# Printing5.net
KiCad netlist of a schematic drawn in Altium Designer
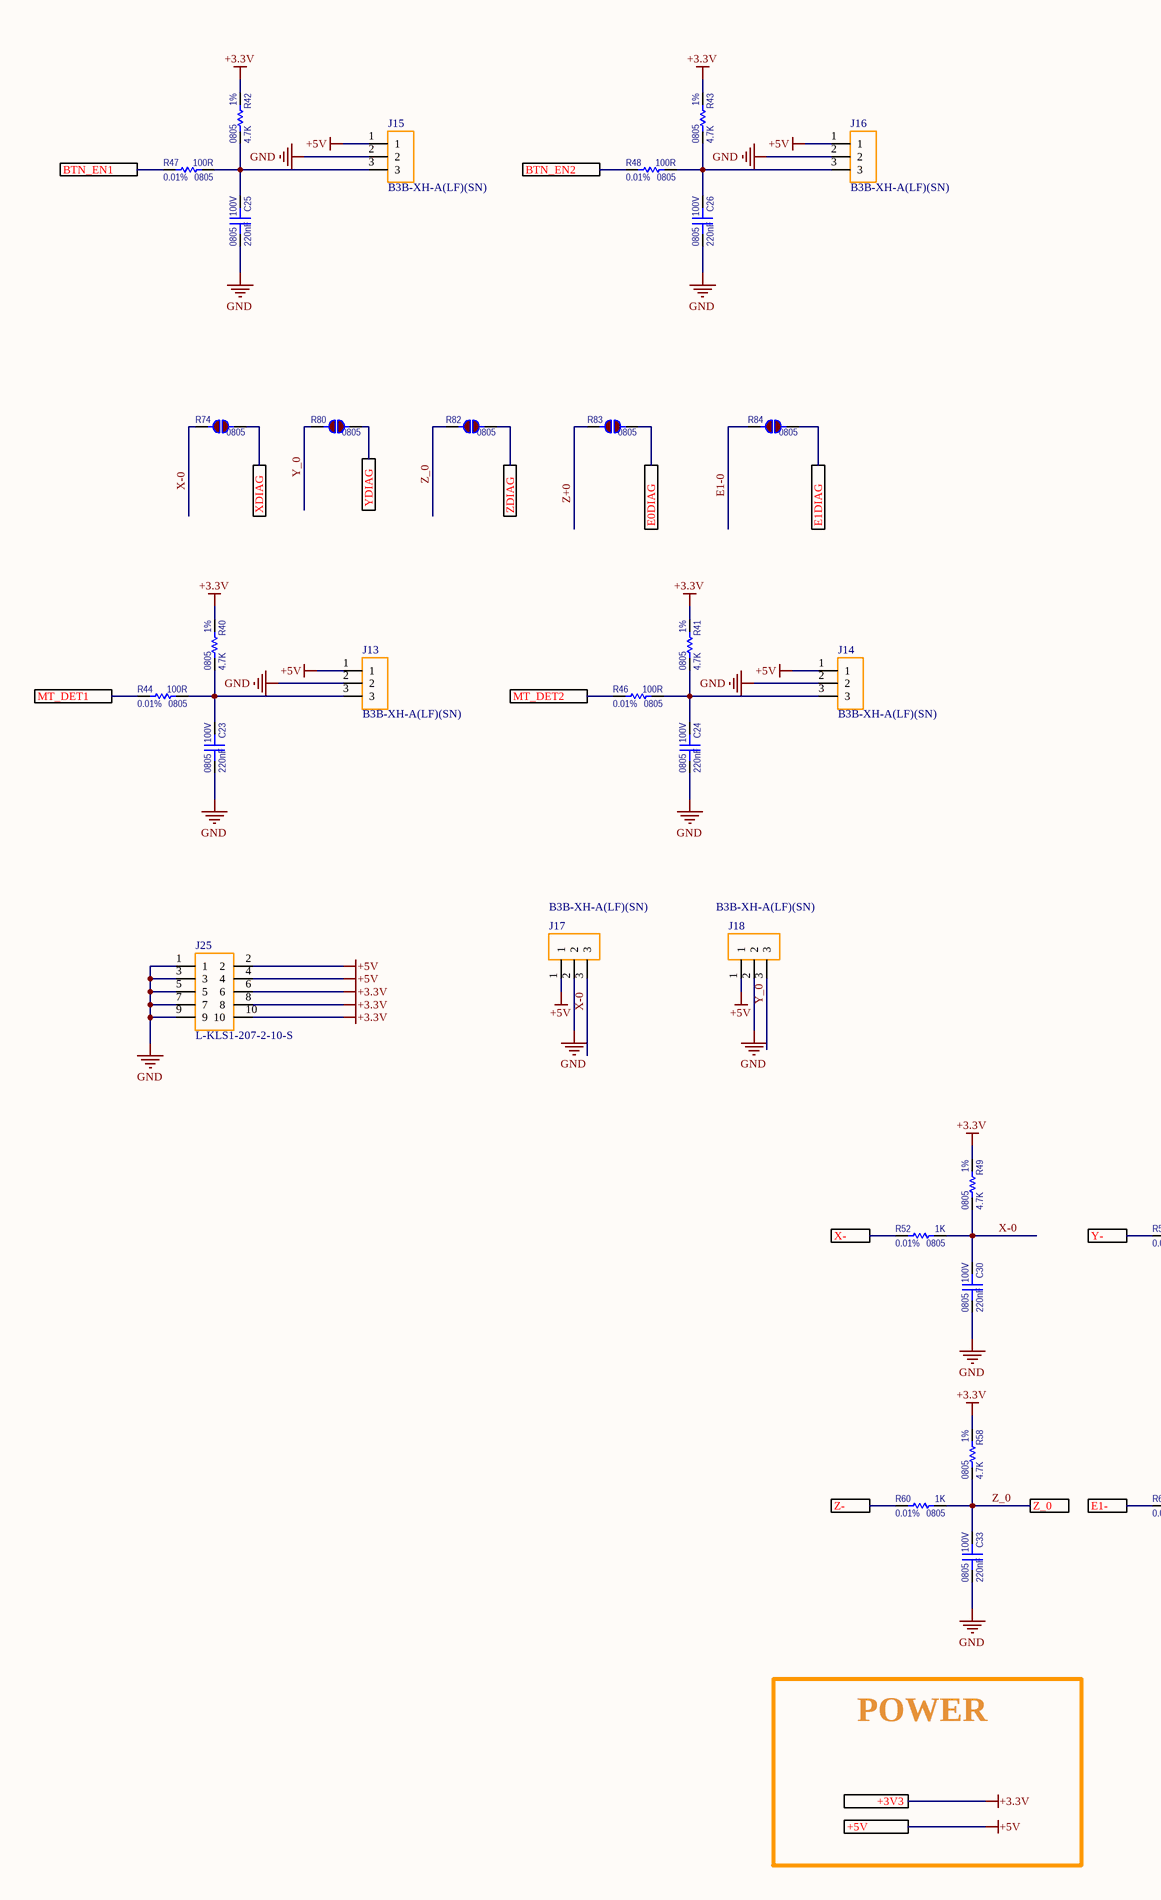
[diagram p0: Printing5.SchDoc, left]
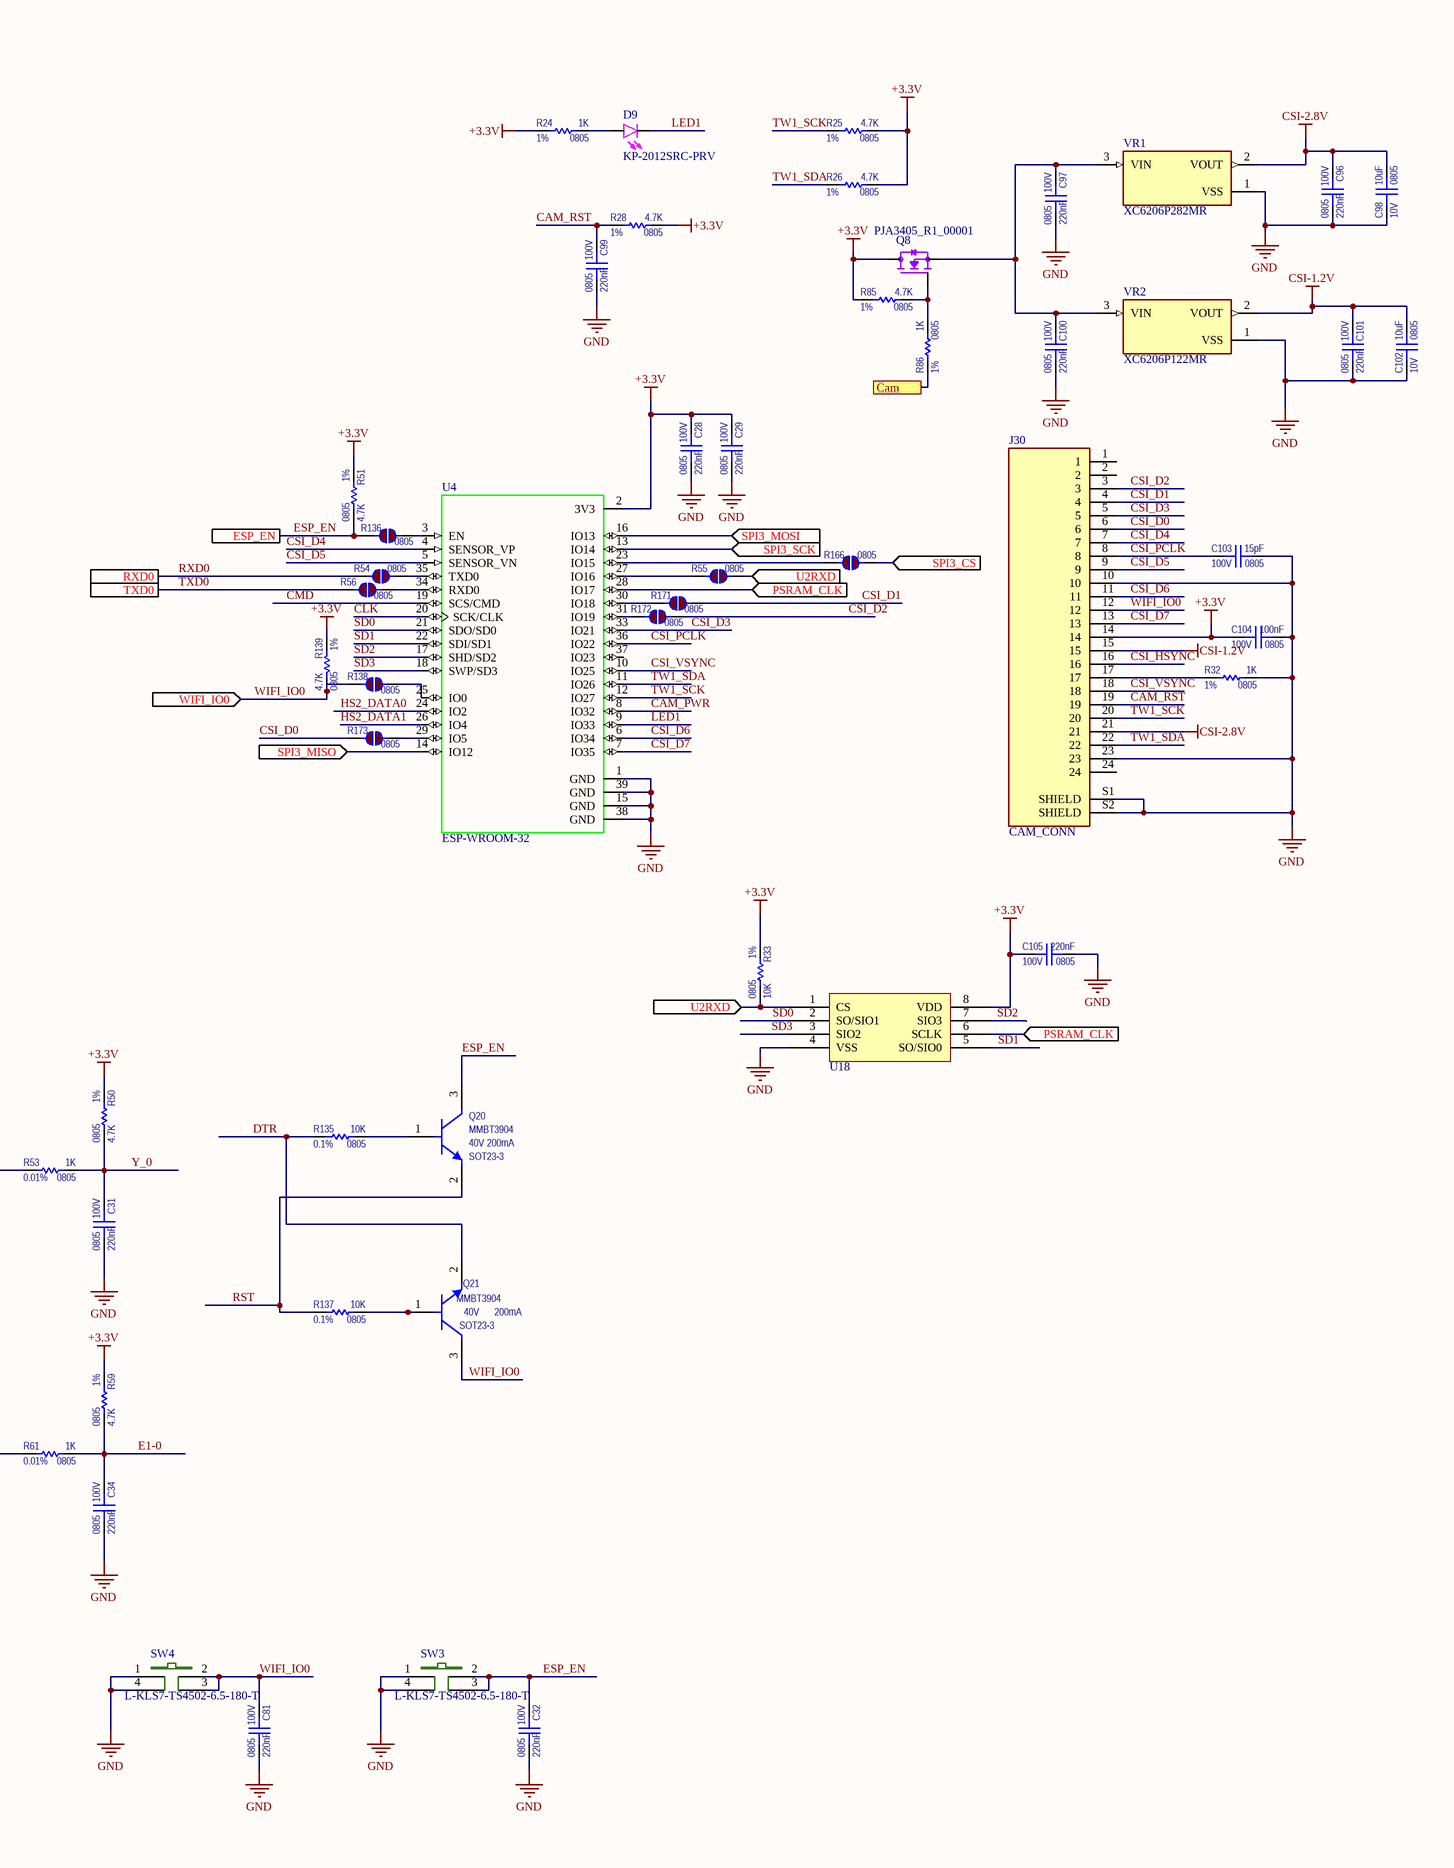
[diagram p1: Printing5.SchDoc, right]

(export (version "E")
  (design (tool "Eeschema 10.0.6"))
  (components
    (comp (ref "C23")
      (value "220nF")
      (footprint "C_0805_GEN_1.40H")
      (description "CAP_CER_220nF_100V_X7R_10%_0805")
      (fields
        (field (name "VOLTAGE") "100V")
        (field (name "PACKAGE") "0805")
        (field (name "SIMILAR PART") "CC0805KKX7R0BB224; GRM21AR72A224KAC5L")
        (field (name "TOLERANCE") "10%")
        (field (name "ADDED BY") "YasinY")
        (field (name "CHECKED BY") "İlkerU")
      )
      (libsource (lib "FireANTs_HwLibDB") (part "Capacitor"))
    )
    (comp (ref "C24")
      (value "220nF")
      (footprint "C_0805_GEN_1.40H")
      (description "CAP_CER_220nF_100V_X7R_10%_0805")
      (fields
        (field (name "VOLTAGE") "100V")
        (field (name "PACKAGE") "0805")
        (field (name "SIMILAR PART") "CC0805KKX7R0BB224; GRM21AR72A224KAC5L")
        (field (name "TOLERANCE") "10%")
        (field (name "ADDED BY") "YasinY")
        (field (name "CHECKED BY") "İlkerU")
      )
      (libsource (lib "FireANTs_HwLibDB") (part "Capacitor"))
    )
    (comp (ref "C25")
      (value "220nF")
      (footprint "C_0805_GEN_1.40H")
      (description "CAP_CER_220nF_100V_X7R_10%_0805")
      (fields
        (field (name "VOLTAGE") "100V")
        (field (name "PACKAGE") "0805")
        (field (name "SIMILAR PART") "CC0805KKX7R0BB224; GRM21AR72A224KAC5L")
        (field (name "TOLERANCE") "10%")
        (field (name "ADDED BY") "YasinY")
        (field (name "CHECKED BY") "İlkerU")
      )
      (libsource (lib "FireANTs_HwLibDB") (part "Capacitor"))
    )
    (comp (ref "C26")
      (value "220nF")
      (footprint "C_0805_GEN_1.40H")
      (description "CAP_CER_220nF_100V_X7R_10%_0805")
      (fields
        (field (name "VOLTAGE") "100V")
        (field (name "PACKAGE") "0805")
        (field (name "SIMILAR PART") "CC0805KKX7R0BB224; GRM21AR72A224KAC5L")
        (field (name "TOLERANCE") "10%")
        (field (name "ADDED BY") "YasinY")
        (field (name "CHECKED BY") "İlkerU")
      )
      (libsource (lib "FireANTs_HwLibDB") (part "Capacitor"))
    )
    (comp (ref "C28")
      (value "220nF")
      (footprint "C_0805_GEN_1.40H")
      (description "CAP_CER_220nF_100V_X7R_10%_0805")
      (fields
        (field (name "VOLTAGE") "100V")
        (field (name "PACKAGE") "0805")
        (field (name "SIMILAR PART") "CC0805KKX7R0BB224; GRM21AR72A224KAC5L")
        (field (name "TOLERANCE") "10%")
        (field (name "ADDED BY") "YasinY")
        (field (name "CHECKED BY") "İlkerU")
      )
      (libsource (lib "FireANTs_HwLibDB") (part "Capacitor"))
    )
    (comp (ref "C29")
      (value "220nF")
      (footprint "C_0805_GEN_1.40H")
      (description "CAP_CER_220nF_100V_X7R_10%_0805")
      (fields
        (field (name "VOLTAGE") "100V")
        (field (name "PACKAGE") "0805")
        (field (name "SIMILAR PART") "CC0805KKX7R0BB224; GRM21AR72A224KAC5L")
        (field (name "TOLERANCE") "10%")
        (field (name "ADDED BY") "YasinY")
        (field (name "CHECKED BY") "İlkerU")
      )
      (libsource (lib "FireANTs_HwLibDB") (part "Capacitor"))
    )
    (comp (ref "C30")
      (value "220nF")
      (footprint "C_0805_GEN_1.40H")
      (description "CAP_CER_220nF_100V_X7R_10%_0805")
      (fields
        (field (name "VOLTAGE") "100V")
        (field (name "PACKAGE") "0805")
        (field (name "SIMILAR PART") "CC0805KKX7R0BB224; GRM21AR72A224KAC5L")
        (field (name "TOLERANCE") "10%")
        (field (name "ADDED BY") "YasinY")
        (field (name "CHECKED BY") "İlkerU")
      )
      (libsource (lib "FireANTs_HwLibDB") (part "Capacitor"))
    )
    (comp (ref "C31")
      (value "220nF")
      (footprint "C_0805_GEN_1.40H")
      (description "CAP_CER_220nF_100V_X7R_10%_0805")
      (fields
        (field (name "VOLTAGE") "100V")
        (field (name "PACKAGE") "0805")
        (field (name "SIMILAR PART") "CC0805KKX7R0BB224; GRM21AR72A224KAC5L")
        (field (name "TOLERANCE") "10%")
        (field (name "ADDED BY") "YasinY")
        (field (name "CHECKED BY") "İlkerU")
      )
      (libsource (lib "FireANTs_HwLibDB") (part "Capacitor"))
    )
    (comp (ref "C32")
      (value "220nF")
      (footprint "C_0805_GEN_1.40H")
      (description "CAP_CER_220nF_100V_X7R_10%_0805")
      (fields
        (field (name "VOLTAGE") "100V")
        (field (name "PACKAGE") "0805")
        (field (name "SIMILAR PART") "CC0805KKX7R0BB224; GRM21AR72A224KAC5L")
        (field (name "TOLERANCE") "10%")
        (field (name "ADDED BY") "YasinY")
        (field (name "CHECKED BY") "İlkerU")
      )
      (libsource (lib "FireANTs_HwLibDB") (part "Capacitor"))
    )
    (comp (ref "C33")
      (value "220nF")
      (footprint "C_0805_GEN_1.40H")
      (description "CAP_CER_220nF_100V_X7R_10%_0805")
      (fields
        (field (name "VOLTAGE") "100V")
        (field (name "PACKAGE") "0805")
        (field (name "SIMILAR PART") "CC0805KKX7R0BB224; GRM21AR72A224KAC5L")
        (field (name "TOLERANCE") "10%")
        (field (name "ADDED BY") "YasinY")
        (field (name "CHECKED BY") "İlkerU")
      )
      (libsource (lib "FireANTs_HwLibDB") (part "Capacitor"))
    )
    (comp (ref "C34")
      (value "220nF")
      (footprint "C_0805_GEN_1.40H")
      (description "CAP_CER_220nF_100V_X7R_10%_0805")
      (fields
        (field (name "VOLTAGE") "100V")
        (field (name "PACKAGE") "0805")
        (field (name "SIMILAR PART") "CC0805KKX7R0BB224; GRM21AR72A224KAC5L")
        (field (name "TOLERANCE") "10%")
        (field (name "ADDED BY") "YasinY")
        (field (name "CHECKED BY") "İlkerU")
      )
      (libsource (lib "FireANTs_HwLibDB") (part "Capacitor"))
    )
    (comp (ref "C81")
      (value "220nF")
      (footprint "C_0805_GEN_1.40H")
      (description "CAP_CER_220nF_100V_X7R_10%_0805")
      (fields
        (field (name "VOLTAGE") "100V")
        (field (name "PACKAGE") "0805")
        (field (name "SIMILAR PART") "CC0805KKX7R0BB224; GRM21AR72A224KAC5L")
        (field (name "TOLERANCE") "10%")
        (field (name "ADDED BY") "YasinY")
        (field (name "CHECKED BY") "İlkerU")
      )
      (libsource (lib "FireANTs_HwLibDB") (part "Capacitor"))
    )
    (comp (ref "C96")
      (value "220nF")
      (footprint "C_0805_GEN_1.40H")
      (description "CAP_CER_220nF_100V_X7R_10%_0805")
      (fields
        (field (name "VOLTAGE") "100V")
        (field (name "PACKAGE") "0805")
        (field (name "SIMILAR PART") "CC0805KKX7R0BB224; GRM21AR72A224KAC5L")
        (field (name "TOLERANCE") "10%")
        (field (name "ADDED BY") "YasinY")
        (field (name "CHECKED BY") "İlkerU")
      )
      (libsource (lib "FireANTs_HwLibDB") (part "Capacitor"))
    )
    (comp (ref "C97")
      (value "220nF")
      (footprint "C_0805_GEN_1.40H")
      (description "CAP_CER_220nF_100V_X7R_10%_0805")
      (fields
        (field (name "VOLTAGE") "100V")
        (field (name "PACKAGE") "0805")
        (field (name "SIMILAR PART") "CC0805KKX7R0BB224; GRM21AR72A224KAC5L")
        (field (name "TOLERANCE") "10%")
        (field (name "ADDED BY") "YasinY")
        (field (name "CHECKED BY") "İlkerU")
      )
      (libsource (lib "FireANTs_HwLibDB") (part "Capacitor"))
    )
    (comp (ref "C98")
      (value "10uF")
      (footprint "C_0805_GEN_1.40H")
      (description "CAP_CER_10uF_10V_X7S_10%_0805")
      (fields
        (field (name "VOLTAGE") "10V")
        (field (name "PACKAGE") "0805")
        (field (name "SIMILAR PART") "C0805C106K8RACAUTO")
        (field (name "TOLERANCE") "10%")
        (field (name "ADDED BY") "HasanA")
        (field (name "CHECKED BY") "İlkerU")
      )
      (libsource (lib "FireANTs_HwLibDB") (part "Capacitor"))
    )
    (comp (ref "C99")
      (value "220nF")
      (footprint "C_0805_GEN_1.40H")
      (description "CAP_CER_220nF_100V_X7R_10%_0805")
      (fields
        (field (name "VOLTAGE") "100V")
        (field (name "PACKAGE") "0805")
        (field (name "SIMILAR PART") "CC0805KKX7R0BB224; GRM21AR72A224KAC5L")
        (field (name "TOLERANCE") "10%")
        (field (name "ADDED BY") "YasinY")
        (field (name "CHECKED BY") "İlkerU")
      )
      (libsource (lib "FireANTs_HwLibDB") (part "Capacitor"))
    )
    (comp (ref "C100")
      (value "220nF")
      (footprint "C_0805_GEN_1.40H")
      (description "CAP_CER_220nF_100V_X7R_10%_0805")
      (fields
        (field (name "VOLTAGE") "100V")
        (field (name "PACKAGE") "0805")
        (field (name "SIMILAR PART") "CC0805KKX7R0BB224; GRM21AR72A224KAC5L")
        (field (name "TOLERANCE") "10%")
        (field (name "ADDED BY") "YasinY")
        (field (name "CHECKED BY") "İlkerU")
      )
      (libsource (lib "FireANTs_HwLibDB") (part "Capacitor"))
    )
    (comp (ref "C101")
      (value "220nF")
      (footprint "C_0805_GEN_1.40H")
      (description "CAP_CER_220nF_100V_X7R_10%_0805")
      (fields
        (field (name "VOLTAGE") "100V")
        (field (name "PACKAGE") "0805")
        (field (name "SIMILAR PART") "CC0805KKX7R0BB224; GRM21AR72A224KAC5L")
        (field (name "TOLERANCE") "10%")
        (field (name "ADDED BY") "YasinY")
        (field (name "CHECKED BY") "İlkerU")
      )
      (libsource (lib "FireANTs_HwLibDB") (part "Capacitor"))
    )
    (comp (ref "C102")
      (value "10uF")
      (footprint "C_0805_GEN_1.40H")
      (description "CAP_CER_10uF_10V_X7S_10%_0805")
      (fields
        (field (name "VOLTAGE") "10V")
        (field (name "PACKAGE") "0805")
        (field (name "SIMILAR PART") "C0805C106K8RACAUTO")
        (field (name "TOLERANCE") "10%")
        (field (name "ADDED BY") "HasanA")
        (field (name "CHECKED BY") "İlkerU")
      )
      (libsource (lib "FireANTs_HwLibDB") (part "Capacitor"))
    )
    (comp (ref "C103")
      (value "15pF")
      (footprint "C_0805_GEN_1.40H")
      (description "CAP_CER_220nF_100V_X7R_10%_0805")
      (fields
        (field (name "VOLTAGE") "100V")
        (field (name "PACKAGE") "0805")
        (field (name "SIMILAR PART") "CC0805KKX7R0BB224; GRM21AR72A224KAC5L")
        (field (name "TOLERANCE") "10%")
        (field (name "ADDED BY") "YasinY")
        (field (name "CHECKED BY") "İlkerU")
      )
      (libsource (lib "FireANTs_HwLibDB") (part "Capacitor"))
    )
    (comp (ref "C104")
      (value "100nF")
      (footprint "C_0805_GEN_1.40H")
      (description "CAP_CER_220nF_100V_X7R_10%_0805")
      (fields
        (field (name "VOLTAGE") "100V")
        (field (name "PACKAGE") "0805")
        (field (name "SIMILAR PART") "CC0805KKX7R0BB224; GRM21AR72A224KAC5L")
        (field (name "TOLERANCE") "10%")
        (field (name "ADDED BY") "YasinY")
        (field (name "CHECKED BY") "İlkerU")
      )
      (libsource (lib "FireANTs_HwLibDB") (part "Capacitor"))
    )
    (comp (ref "C105")
      (value "220nF")
      (footprint "C_0805_GEN_1.40H")
      (description "CAP_CER_220nF_100V_X7R_10%_0805")
      (fields
        (field (name "VOLTAGE") "100V")
        (field (name "PACKAGE") "0805")
        (field (name "SIMILAR PART") "CC0805KKX7R0BB224; GRM21AR72A224KAC5L")
        (field (name "TOLERANCE") "10%")
        (field (name "ADDED BY") "YasinY")
        (field (name "CHECKED BY") "İlkerU")
      )
      (libsource (lib "FireANTs_HwLibDB") (part "Capacitor"))
    )
    (comp (ref "D9")
      (value "KP-2012SRC-PRV")
      (footprint "0805 LED")
      (description "KP-2012SRC-PRV Red LED, 640 nm 2012 (0805), Rectangle Lens SMD package")
      (fields (field (name "MANUFACTURER") "Kingbright"))
      (libsource (lib "Printing") (part "KP-2012SRC-PRV"))
    )
    (comp (ref "J13")
      (value "B3B-XH-A(LF)(SN)")
      (footprint "JST_B3B-XH-A(LF)(SN)")
      (libsource (lib "") (part "B3B-XH-A(LF)(SN)_1"))
    )
    (comp (ref "J14")
      (value "B3B-XH-A(LF)(SN)")
      (footprint "JST_B3B-XH-A(LF)(SN)")
      (libsource (lib "") (part "B3B-XH-A(LF)(SN)_1"))
    )
    (comp (ref "J15")
      (value "B3B-XH-A(LF)(SN)")
      (footprint "JST_B3B-XH-A(LF)(SN)")
      (libsource (lib "") (part "B3B-XH-A(LF)(SN)_1"))
    )
    (comp (ref "J16")
      (value "B3B-XH-A(LF)(SN)")
      (footprint "JST_B3B-XH-A(LF)(SN)")
      (libsource (lib "") (part "B3B-XH-A(LF)(SN)_1"))
    )
    (comp (ref "J17")
      (value "B3B-XH-A(LF)(SN)")
      (footprint "JST_B3B-XH-A(LF)(SN)")
      (libsource (lib "Printing") (part "B3B-XH-A(LF)(SN)"))
    )
    (comp (ref "J18")
      (value "B3B-XH-A(LF)(SN)")
      (footprint "JST_B3B-XH-A(LF)(SN)")
      (libsource (lib "Printing") (part "B3B-XH-A(LF)(SN)"))
    )
    (comp (ref "J25")
      (value "L-KLS1-207-2-10-S")
      (footprint "L-KLS1-207-2-10-S")
      (libsource (lib "Printing") (part "L-KLS1-207-2-10-S"))
    )
    (comp (ref "J30")
      (value "CAM_CONN")
      (footprint "CAM_CONN")
      (libsource (lib "Printing") (part "CAM_CONN"))
    )
    (comp (ref "Q8")
      (value "PJA3405_R1_00001")
      (footprint "PJA3405_R1_00001")
      (fields (field (name "MANUFACTURER") "Pan Jit"))
      (libsource (lib "Printing") (part "PJA3405_R1_00001"))
    )
    (comp (ref "Q20")
      (value "MMBT3904")
      (footprint "SOT23-3_MMBT3904,215")
      (description "TRA_NPN_SING_40V_200mA_VSAT300mV_SOT23-3")
      (fields
        (field (name "CURRENT") "200mA")
        (field (name "VOLTAGE") "40V")
        (field (name "PACKAGE") "SOT23-3")
        (field (name "SIMILAR PART") "SST3904HZGT116; PMBT3904,235")
        (field (name "TOLERANCE") "X")
        (field (name "ADDED BY") "HasanA")
        (field (name "CHECKED BY") "EserC")
      )
      (libsource (lib "FireANTs_HwLibDB") (part "SingleNPN_B1E2C3"))
    )
    (comp (ref "Q21")
      (value "MMBT3904")
      (footprint "SOT23-3_MMBT3904,215")
      (description "TRA_NPN_SING_40V_200mA_VSAT300mV_SOT23-3")
      (fields
        (field (name "CURRENT") "200mA")
        (field (name "VOLTAGE") "40V")
        (field (name "PACKAGE") "SOT23-3")
        (field (name "SIMILAR PART") "SST3904HZGT116; PMBT3904,235")
        (field (name "TOLERANCE") "X")
        (field (name "ADDED BY") "HasanA")
        (field (name "CHECKED BY") "EserC")
      )
      (libsource (lib "FireANTs_HwLibDB") (part "SingleNPN_B1E2C3"))
    )
    (comp (ref "R24")
      (value "1K")
      (footprint "R_0805_GEN_0.60H")
      (description "RES_STD_4.7K_0.125W_1%_100ppm_0805")
      (fields
        (field (name "TOLERANCE") "1%")
        (field (name "PACKAGE") "0805")
        (field (name "VOLTAGE") "150V")
        (field (name "Comment") "StandardResistor")
        (field (name "ADDED BY") "SonerI")
        (field (name "CHECKED BY") "YasinY")
      )
      (libsource (lib "FireANTs_HwLibDB") (part "StandardResistor"))
    )
    (comp (ref "R25")
      (value "4.7K")
      (footprint "R_0805_GEN_0.60H")
      (description "RES_STD_4.7K_0.125W_1%_100ppm_0805")
      (fields
        (field (name "TOLERANCE") "1%")
        (field (name "PACKAGE") "0805")
        (field (name "VOLTAGE") "150V")
        (field (name "Comment") "StandardResistor")
        (field (name "ADDED BY") "SonerI")
        (field (name "CHECKED BY") "YasinY")
      )
      (libsource (lib "FireANTs_HwLibDB") (part "StandardResistor"))
    )
    (comp (ref "R26")
      (value "4.7K")
      (footprint "R_0805_GEN_0.60H")
      (description "RES_STD_4.7K_0.125W_1%_100ppm_0805")
      (fields
        (field (name "TOLERANCE") "1%")
        (field (name "PACKAGE") "0805")
        (field (name "VOLTAGE") "150V")
        (field (name "Comment") "StandardResistor")
        (field (name "ADDED BY") "SonerI")
        (field (name "CHECKED BY") "YasinY")
      )
      (libsource (lib "FireANTs_HwLibDB") (part "StandardResistor"))
    )
    (comp (ref "R28")
      (value "4.7K")
      (footprint "R_0805_GEN_0.60H")
      (description "RES_STD_4.7K_0.125W_1%_100ppm_0805")
      (fields
        (field (name "TOLERANCE") "1%")
        (field (name "PACKAGE") "0805")
        (field (name "VOLTAGE") "150V")
        (field (name "Comment") "StandardResistor")
        (field (name "ADDED BY") "SonerI")
        (field (name "CHECKED BY") "YasinY")
      )
      (libsource (lib "FireANTs_HwLibDB") (part "StandardResistor"))
    )
    (comp (ref "R32")
      (value "1K")
      (footprint "R_0805_GEN_0.60H")
      (description "RES_STD_4.7K_0.125W_1%_100ppm_0805")
      (fields
        (field (name "TOLERANCE") "1%")
        (field (name "PACKAGE") "0805")
        (field (name "VOLTAGE") "150V")
        (field (name "Comment") "StandardResistor")
        (field (name "ADDED BY") "SonerI")
        (field (name "CHECKED BY") "YasinY")
      )
      (libsource (lib "FireANTs_HwLibDB") (part "StandardResistor"))
    )
    (comp (ref "R33")
      (value "10K")
      (footprint "R_0805_GEN_0.60H")
      (description "RES_STD_4.7K_0.125W_1%_100ppm_0805")
      (fields
        (field (name "TOLERANCE") "1%")
        (field (name "PACKAGE") "0805")
        (field (name "VOLTAGE") "150V")
        (field (name "Comment") "StandardResistor")
        (field (name "ADDED BY") "SonerI")
        (field (name "CHECKED BY") "YasinY")
      )
      (libsource (lib "FireANTs_HwLibDB") (part "StandardResistor"))
    )
    (comp (ref "R40")
      (value "4.7K")
      (footprint "R_0805_GEN_0.60H")
      (description "RES_STD_4.7K_0.125W_1%_100ppm_0805")
      (fields
        (field (name "TOLERANCE") "1%")
        (field (name "PACKAGE") "0805")
        (field (name "VOLTAGE") "150V")
        (field (name "Comment") "StandardResistor")
        (field (name "ADDED BY") "SonerI")
        (field (name "CHECKED BY") "YasinY")
      )
      (libsource (lib "FireANTs_HwLibDB") (part "StandardResistor"))
    )
    (comp (ref "R41")
      (value "4.7K")
      (footprint "R_0805_GEN_0.60H")
      (description "RES_STD_4.7K_0.125W_1%_100ppm_0805")
      (fields
        (field (name "TOLERANCE") "1%")
        (field (name "PACKAGE") "0805")
        (field (name "VOLTAGE") "150V")
        (field (name "Comment") "StandardResistor")
        (field (name "ADDED BY") "SonerI")
        (field (name "CHECKED BY") "YasinY")
      )
      (libsource (lib "FireANTs_HwLibDB") (part "StandardResistor"))
    )
    (comp (ref "R42")
      (value "4.7K")
      (footprint "R_0805_GEN_0.60H")
      (description "RES_STD_4.7K_0.125W_1%_100ppm_0805")
      (fields
        (field (name "TOLERANCE") "1%")
        (field (name "PACKAGE") "0805")
        (field (name "VOLTAGE") "150V")
        (field (name "Comment") "StandardResistor")
        (field (name "ADDED BY") "SonerI")
        (field (name "CHECKED BY") "YasinY")
      )
      (libsource (lib "FireANTs_HwLibDB") (part "StandardResistor"))
    )
    (comp (ref "R43")
      (value "4.7K")
      (footprint "R_0805_GEN_0.60H")
      (description "RES_STD_4.7K_0.125W_1%_100ppm_0805")
      (fields
        (field (name "TOLERANCE") "1%")
        (field (name "PACKAGE") "0805")
        (field (name "VOLTAGE") "150V")
        (field (name "Comment") "StandardResistor")
        (field (name "ADDED BY") "SonerI")
        (field (name "CHECKED BY") "YasinY")
      )
      (libsource (lib "FireANTs_HwLibDB") (part "StandardResistor"))
    )
    (comp (ref "R44")
      (value "100R")
      (footprint "R_0805_GEN_0.70H")
      (description "RES_STD_100R_0.125W_0.01%_5ppm_0805")
      (fields
        (field (name "TOLERANCE") "0.01%")
        (field (name "PACKAGE") "0805")
        (field (name "VOLTAGE") "150V")
        (field (name "Comment") "StandardResistor")
        (field (name "ADDED BY") "HasanA")
        (field (name "CHECKED BY") "YasinY")
      )
      (libsource (lib "FireANTs_HwLibDB") (part "StandardResistor"))
    )
    (comp (ref "R46")
      (value "100R")
      (footprint "R_0805_GEN_0.70H")
      (description "RES_STD_100R_0.125W_0.01%_5ppm_0805")
      (fields
        (field (name "TOLERANCE") "0.01%")
        (field (name "PACKAGE") "0805")
        (field (name "VOLTAGE") "150V")
        (field (name "Comment") "StandardResistor")
        (field (name "ADDED BY") "HasanA")
        (field (name "CHECKED BY") "YasinY")
      )
      (libsource (lib "FireANTs_HwLibDB") (part "StandardResistor"))
    )
    (comp (ref "R47")
      (value "100R")
      (footprint "R_0805_GEN_0.70H")
      (description "RES_STD_100R_0.125W_0.01%_5ppm_0805")
      (fields
        (field (name "TOLERANCE") "0.01%")
        (field (name "PACKAGE") "0805")
        (field (name "VOLTAGE") "150V")
        (field (name "Comment") "StandardResistor")
        (field (name "ADDED BY") "HasanA")
        (field (name "CHECKED BY") "YasinY")
      )
      (libsource (lib "FireANTs_HwLibDB") (part "StandardResistor"))
    )
    (comp (ref "R48")
      (value "100R")
      (footprint "R_0805_GEN_0.70H")
      (description "RES_STD_100R_0.125W_0.01%_5ppm_0805")
      (fields
        (field (name "TOLERANCE") "0.01%")
        (field (name "PACKAGE") "0805")
        (field (name "VOLTAGE") "150V")
        (field (name "Comment") "StandardResistor")
        (field (name "ADDED BY") "HasanA")
        (field (name "CHECKED BY") "YasinY")
      )
      (libsource (lib "FireANTs_HwLibDB") (part "StandardResistor"))
    )
    (comp (ref "R49")
      (value "4.7K")
      (footprint "R_0805_GEN_0.60H")
      (description "RES_STD_4.7K_0.125W_1%_100ppm_0805")
      (fields
        (field (name "TOLERANCE") "1%")
        (field (name "PACKAGE") "0805")
        (field (name "VOLTAGE") "150V")
        (field (name "Comment") "StandardResistor")
        (field (name "ADDED BY") "SonerI")
        (field (name "CHECKED BY") "YasinY")
      )
      (libsource (lib "FireANTs_HwLibDB") (part "StandardResistor"))
    )
    (comp (ref "R50")
      (value "4.7K")
      (footprint "R_0805_GEN_0.60H")
      (description "RES_STD_4.7K_0.125W_1%_100ppm_0805")
      (fields
        (field (name "TOLERANCE") "1%")
        (field (name "PACKAGE") "0805")
        (field (name "VOLTAGE") "150V")
        (field (name "Comment") "StandardResistor")
        (field (name "ADDED BY") "SonerI")
        (field (name "CHECKED BY") "YasinY")
      )
      (libsource (lib "FireANTs_HwLibDB") (part "StandardResistor"))
    )
    (comp (ref "R51")
      (value "4.7K")
      (footprint "R_0805_GEN_0.60H")
      (description "RES_STD_4.7K_0.125W_1%_100ppm_0805")
      (fields
        (field (name "TOLERANCE") "1%")
        (field (name "PACKAGE") "0805")
        (field (name "VOLTAGE") "150V")
        (field (name "Comment") "StandardResistor")
        (field (name "ADDED BY") "SonerI")
        (field (name "CHECKED BY") "YasinY")
      )
      (libsource (lib "FireANTs_HwLibDB") (part "StandardResistor"))
    )
    (comp (ref "R52")
      (value "1K")
      (footprint "R_0805_GEN_0.70H")
      (description "RES_STD_1K_0.125W_0.01%_5ppm_0805")
      (fields
        (field (name "TOLERANCE") "0.01%")
        (field (name "PACKAGE") "0805")
        (field (name "SIMILAR PART") "PLTU0805U1001LST5")
        (field (name "VOLTAGE") "150V")
        (field (name "ADDED BY") "HasanA")
        (field (name "CHECKED BY") "YasinY")
      )
      (libsource (lib "FireANTs_HwLibDB") (part "StandardResistor"))
    )
    (comp (ref "R53")
      (value "1K")
      (footprint "R_0805_GEN_0.70H")
      (description "RES_STD_1K_0.125W_0.01%_5ppm_0805")
      (fields
        (field (name "TOLERANCE") "0.01%")
        (field (name "PACKAGE") "0805")
        (field (name "SIMILAR PART") "PLTU0805U1001LST5")
        (field (name "VOLTAGE") "150V")
        (field (name "ADDED BY") "HasanA")
        (field (name "CHECKED BY") "YasinY")
      )
      (libsource (lib "FireANTs_HwLibDB") (part "StandardResistor"))
    )
    (comp (ref "R54")
      (value "StandardJumper")
      (footprint "R_0805_GEN_0.70H")
      (description "RES_STD_0R_0.125W_0805")
      (fields
        (field (name "PACKAGE") "0805")
        (field (name "TOLERANCE") "5%")
        (field (name "VOLTAGE") "150V")
        (field (name "ADDED BY") "İlhanT")
        (field (name "CHECKED BY") "YasinY")
      )
      (libsource (lib "FireANTs_HwLibDB") (part "StandardJumper"))
    )
    (comp (ref "R55")
      (value "StandardJumper")
      (footprint "R_0805_GEN_0.70H")
      (description "RES_STD_0R_0.125W_0805")
      (fields
        (field (name "PACKAGE") "0805")
        (field (name "TOLERANCE") "5%")
        (field (name "VOLTAGE") "150V")
        (field (name "ADDED BY") "İlhanT")
        (field (name "CHECKED BY") "YasinY")
      )
      (libsource (lib "FireANTs_HwLibDB") (part "StandardJumper"))
    )
    (comp (ref "R56")
      (value "StandardJumper")
      (footprint "R_0805_GEN_0.70H")
      (description "RES_STD_0R_0.125W_0805")
      (fields
        (field (name "PACKAGE") "0805")
        (field (name "TOLERANCE") "5%")
        (field (name "VOLTAGE") "150V")
        (field (name "ADDED BY") "İlhanT")
        (field (name "CHECKED BY") "YasinY")
      )
      (libsource (lib "FireANTs_HwLibDB") (part "StandardJumper"))
    )
    (comp (ref "R58")
      (value "4.7K")
      (footprint "R_0805_GEN_0.60H")
      (description "RES_STD_4.7K_0.125W_1%_100ppm_0805")
      (fields
        (field (name "TOLERANCE") "1%")
        (field (name "PACKAGE") "0805")
        (field (name "VOLTAGE") "150V")
        (field (name "Comment") "StandardResistor")
        (field (name "ADDED BY") "SonerI")
        (field (name "CHECKED BY") "YasinY")
      )
      (libsource (lib "FireANTs_HwLibDB") (part "StandardResistor"))
    )
    (comp (ref "R59")
      (value "4.7K")
      (footprint "R_0805_GEN_0.60H")
      (description "RES_STD_4.7K_0.125W_1%_100ppm_0805")
      (fields
        (field (name "TOLERANCE") "1%")
        (field (name "PACKAGE") "0805")
        (field (name "VOLTAGE") "150V")
        (field (name "Comment") "StandardResistor")
        (field (name "ADDED BY") "SonerI")
        (field (name "CHECKED BY") "YasinY")
      )
      (libsource (lib "FireANTs_HwLibDB") (part "StandardResistor"))
    )
    (comp (ref "R60")
      (value "1K")
      (footprint "R_0805_GEN_0.70H")
      (description "RES_STD_1K_0.125W_0.01%_5ppm_0805")
      (fields
        (field (name "TOLERANCE") "0.01%")
        (field (name "PACKAGE") "0805")
        (field (name "SIMILAR PART") "PLTU0805U1001LST5")
        (field (name "VOLTAGE") "150V")
        (field (name "ADDED BY") "HasanA")
        (field (name "CHECKED BY") "YasinY")
      )
      (libsource (lib "FireANTs_HwLibDB") (part "StandardResistor"))
    )
    (comp (ref "R61")
      (value "1K")
      (footprint "R_0805_GEN_0.70H")
      (description "RES_STD_1K_0.125W_0.01%_5ppm_0805")
      (fields
        (field (name "TOLERANCE") "0.01%")
        (field (name "PACKAGE") "0805")
        (field (name "SIMILAR PART") "PLTU0805U1001LST5")
        (field (name "VOLTAGE") "150V")
        (field (name "ADDED BY") "HasanA")
        (field (name "CHECKED BY") "YasinY")
      )
      (libsource (lib "FireANTs_HwLibDB") (part "StandardResistor"))
    )
    (comp (ref "R74")
      (value "StandardJumper")
      (footprint "R_0805_GEN_0.70H")
      (description "RES_STD_0R_0.125W_0805")
      (fields
        (field (name "PACKAGE") "0805")
        (field (name "TOLERANCE") "5%")
        (field (name "VOLTAGE") "150V")
        (field (name "ADDED BY") "İlhanT")
        (field (name "CHECKED BY") "YasinY")
      )
      (libsource (lib "FireANTs_HwLibDB") (part "StandardJumper"))
    )
    (comp (ref "R80")
      (value "StandardJumper")
      (footprint "R_0805_GEN_0.70H")
      (description "RES_STD_0R_0.125W_0805")
      (fields
        (field (name "PACKAGE") "0805")
        (field (name "TOLERANCE") "5%")
        (field (name "VOLTAGE") "150V")
        (field (name "ADDED BY") "İlhanT")
        (field (name "CHECKED BY") "YasinY")
      )
      (libsource (lib "FireANTs_HwLibDB") (part "StandardJumper"))
    )
    (comp (ref "R82")
      (value "StandardJumper")
      (footprint "R_0805_GEN_0.70H")
      (description "RES_STD_0R_0.125W_0805")
      (fields
        (field (name "PACKAGE") "0805")
        (field (name "TOLERANCE") "5%")
        (field (name "VOLTAGE") "150V")
        (field (name "ADDED BY") "İlhanT")
        (field (name "CHECKED BY") "YasinY")
      )
      (libsource (lib "FireANTs_HwLibDB") (part "StandardJumper"))
    )
    (comp (ref "R83")
      (value "StandardJumper")
      (footprint "R_0805_GEN_0.70H")
      (description "RES_STD_0R_0.125W_0805")
      (fields
        (field (name "PACKAGE") "0805")
        (field (name "TOLERANCE") "5%")
        (field (name "VOLTAGE") "150V")
        (field (name "ADDED BY") "İlhanT")
        (field (name "CHECKED BY") "YasinY")
      )
      (libsource (lib "FireANTs_HwLibDB") (part "StandardJumper"))
    )
    (comp (ref "R84")
      (value "StandardJumper")
      (footprint "R_0805_GEN_0.70H")
      (description "RES_STD_0R_0.125W_0805")
      (fields
        (field (name "PACKAGE") "0805")
        (field (name "TOLERANCE") "5%")
        (field (name "VOLTAGE") "150V")
        (field (name "ADDED BY") "İlhanT")
        (field (name "CHECKED BY") "YasinY")
      )
      (libsource (lib "FireANTs_HwLibDB") (part "StandardJumper"))
    )
    (comp (ref "R85")
      (value "4.7K")
      (footprint "R_0805_GEN_0.60H")
      (description "RES_STD_4.7K_0.125W_1%_100ppm_0805")
      (fields
        (field (name "TOLERANCE") "1%")
        (field (name "PACKAGE") "0805")
        (field (name "VOLTAGE") "150V")
        (field (name "Comment") "StandardResistor")
        (field (name "ADDED BY") "SonerI")
        (field (name "CHECKED BY") "YasinY")
      )
      (libsource (lib "FireANTs_HwLibDB") (part "StandardResistor"))
    )
    (comp (ref "R86")
      (value "1K")
      (footprint "R_0805_GEN_0.60H")
      (description "RES_STD_4.7K_0.125W_1%_100ppm_0805")
      (fields
        (field (name "TOLERANCE") "1%")
        (field (name "PACKAGE") "0805")
        (field (name "VOLTAGE") "150V")
        (field (name "Comment") "StandardResistor")
        (field (name "ADDED BY") "SonerI")
        (field (name "CHECKED BY") "YasinY")
      )
      (libsource (lib "FireANTs_HwLibDB") (part "StandardResistor"))
    )
    (comp (ref "R135")
      (value "10K")
      (footprint "R_0805_GEN_0.70H")
      (description "RES_STD_10K_0.125W_0.1%_25ppm_0805")
      (fields
        (field (name "TOLERANCE") "0.1%")
        (field (name "PACKAGE") "0805")
        (field (name "SIMILAR PART") "RN73C2A10KBTD")
        (field (name "VOLTAGE") "100V")
        (field (name "ADDED BY") "İlhanT")
        (field (name "CHECKED BY") "YasinY")
      )
      (libsource (lib "FireANTs_HwLibDB") (part "StandardResistor"))
    )
    (comp (ref "R136")
      (value "StandardJumper")
      (footprint "R_0805_GEN_0.70H")
      (description "RES_STD_0R_0.125W_0805")
      (fields
        (field (name "PACKAGE") "0805")
        (field (name "TOLERANCE") "5%")
        (field (name "VOLTAGE") "150V")
        (field (name "ADDED BY") "İlhanT")
        (field (name "CHECKED BY") "YasinY")
      )
      (libsource (lib "FireANTs_HwLibDB") (part "StandardJumper"))
    )
    (comp (ref "R137")
      (value "10K")
      (footprint "R_0805_GEN_0.70H")
      (description "RES_STD_10K_0.125W_0.1%_25ppm_0805")
      (fields
        (field (name "TOLERANCE") "0.1%")
        (field (name "PACKAGE") "0805")
        (field (name "SIMILAR PART") "RN73C2A10KBTD")
        (field (name "VOLTAGE") "100V")
        (field (name "ADDED BY") "İlhanT")
        (field (name "CHECKED BY") "YasinY")
      )
      (libsource (lib "FireANTs_HwLibDB") (part "StandardResistor"))
    )
    (comp (ref "R138")
      (value "StandardJumper")
      (footprint "R_0805_GEN_0.70H")
      (description "RES_STD_0R_0.125W_0805")
      (fields
        (field (name "PACKAGE") "0805")
        (field (name "TOLERANCE") "5%")
        (field (name "VOLTAGE") "150V")
        (field (name "ADDED BY") "İlhanT")
        (field (name "CHECKED BY") "YasinY")
      )
      (libsource (lib "FireANTs_HwLibDB") (part "StandardJumper"))
    )
    (comp (ref "R139")
      (value "4.7K")
      (footprint "R_0805_GEN_0.60H")
      (description "RES_STD_4.7K_0.125W_1%_100ppm_0805")
      (fields
        (field (name "TOLERANCE") "1%")
        (field (name "PACKAGE") "0805")
        (field (name "VOLTAGE") "150V")
        (field (name "Comment") "StandardResistor")
        (field (name "ADDED BY") "SonerI")
        (field (name "CHECKED BY") "YasinY")
      )
      (libsource (lib "FireANTs_HwLibDB") (part "StandardResistor"))
    )
    (comp (ref "R166")
      (value "StandardJumper")
      (footprint "R_0805_GEN_0.70H")
      (description "RES_STD_0R_0.125W_0805")
      (fields
        (field (name "PACKAGE") "0805")
        (field (name "TOLERANCE") "5%")
        (field (name "VOLTAGE") "150V")
        (field (name "ADDED BY") "İlhanT")
        (field (name "CHECKED BY") "YasinY")
      )
      (libsource (lib "FireANTs_HwLibDB") (part "StandardJumper"))
    )
    (comp (ref "R171")
      (value "StandardJumper")
      (footprint "R_0805_GEN_0.70H")
      (description "RES_STD_0R_0.125W_0805")
      (fields
        (field (name "PACKAGE") "0805")
        (field (name "TOLERANCE") "5%")
        (field (name "VOLTAGE") "150V")
        (field (name "ADDED BY") "İlhanT")
        (field (name "CHECKED BY") "YasinY")
      )
      (libsource (lib "FireANTs_HwLibDB") (part "StandardJumper"))
    )
    (comp (ref "R172")
      (value "StandardJumper")
      (footprint "R_0805_GEN_0.70H")
      (description "RES_STD_0R_0.125W_0805")
      (fields
        (field (name "PACKAGE") "0805")
        (field (name "TOLERANCE") "5%")
        (field (name "VOLTAGE") "150V")
        (field (name "ADDED BY") "İlhanT")
        (field (name "CHECKED BY") "YasinY")
      )
      (libsource (lib "FireANTs_HwLibDB") (part "StandardJumper"))
    )
    (comp (ref "R173")
      (value "StandardJumper")
      (footprint "R_0805_GEN_0.70H")
      (description "RES_STD_0R_0.125W_0805")
      (fields
        (field (name "PACKAGE") "0805")
        (field (name "TOLERANCE") "5%")
        (field (name "VOLTAGE") "150V")
        (field (name "ADDED BY") "İlhanT")
        (field (name "CHECKED BY") "YasinY")
      )
      (libsource (lib "FireANTs_HwLibDB") (part "StandardJumper"))
    )
    (comp (ref "SW3")
      (value "L-KLS7-TS4502-6.5-180-T")
      (footprint "L-KLS7-TS4502-6.5-180-T")
      (libsource (lib "Printing") (part "L-KLS7-TS4502-6.5-180-T"))
    )
    (comp (ref "SW4")
      (value "L-KLS7-TS4502-6.5-180-T")
      (footprint "L-KLS7-TS4502-6.5-180-T")
      (libsource (lib "Printing") (part "L-KLS7-TS4502-6.5-180-T"))
    )
    (comp (ref "U4")
      (value "ESP-WROOM-32")
      (footprint "ESP_DUAL")
      (libsource (lib "Printing") (part "ESP-WROOM-32"))
    )
    (comp (ref "U18")
      (value "PSRAM_ESP32")
      (footprint "SOP8")
      (libsource (lib "Printing") (part "PSRAM_ESP32"))
    )
    (comp (ref "VR1")
      (value "XC6206P282MR")
      (footprint "SOT95P280X130-3N")
      (description "Linear Voltage Regulator IC 1 Output 200mA SOT-23")
      (fields (field (name "MP") "XC6206P302MR"))
      (libsource (lib "Printing") (part "XC6206P302MR"))
    )
    (comp (ref "VR2")
      (value "XC6206P122MR")
      (footprint "SOT95P280X130-3N")
      (description "Linear Voltage Regulator IC 1 Output 200mA SOT-23")
      (fields (field (name "MP") "XC6206P302MR"))
      (libsource (lib "Printing") (part "XC6206P302MR"))
    )
  )
  (nets
    (net (code "1") (name "+3.3V") (class "Default")
      (node (ref "C104") (pin "1") (pinfunction "1_1") (pintype "passive"))
      (node (ref "C105") (pin "1") (pinfunction "1_1") (pintype "passive"))
      (node (ref "C28") (pin "1") (pinfunction "1_1") (pintype "passive"))
      (node (ref "C29") (pin "1") (pinfunction "1_1") (pintype "passive"))
      (node (ref "J25") (pin "10") (pinfunction "10_10") (pintype "passive"))
      (node (ref "J25") (pin "6") (pinfunction "6_6") (pintype "passive"))
      (node (ref "J25") (pin "8") (pinfunction "8_8") (pintype "passive"))
      (node (ref "J30") (pin "14") (pinfunction "14_14") (pintype "passive"))
      (node (ref "Q8") (pin "3") (pinfunction "D_3") (pintype "passive"))
      (node (ref "R139") (pin "1") (pinfunction "1_1") (pintype "passive"))
      (node (ref "R24") (pin "1") (pinfunction "1_1") (pintype "passive"))
      (node (ref "R25") (pin "2") (pinfunction "2_2") (pintype "passive"))
      (node (ref "R26") (pin "2") (pinfunction "2_2") (pintype "passive"))
      (node (ref "R28") (pin "2") (pinfunction "2_2") (pintype "passive"))
      (node (ref "R33") (pin "1") (pinfunction "1_1") (pintype "passive"))
      (node (ref "R40") (pin "1") (pinfunction "1_1") (pintype "passive"))
      (node (ref "R41") (pin "1") (pinfunction "1_1") (pintype "passive"))
      (node (ref "R42") (pin "1") (pinfunction "1_1") (pintype "passive"))
      (node (ref "R43") (pin "1") (pinfunction "1_1") (pintype "passive"))
      (node (ref "R49") (pin "1") (pinfunction "1_1") (pintype "passive"))
      (node (ref "R50") (pin "1") (pinfunction "1_1") (pintype "passive"))
      (node (ref "R51") (pin "1") (pinfunction "1_1") (pintype "passive"))
      (node (ref "R58") (pin "1") (pinfunction "1_1") (pintype "passive"))
      (node (ref "R59") (pin "1") (pinfunction "1_1") (pintype "passive"))
      (node (ref "R85") (pin "1") (pinfunction "1_1") (pintype "passive"))
      (node (ref "U18") (pin "8") (pinfunction "VDD_8") (pintype "passive"))
      (node (ref "U4") (pin "2") (pinfunction "3V3_2") (pintype "power_in"))
    )
    (net (code "2") (name "+5V") (class "Default")
      (node (ref "J13") (pin "1") (pinfunction "1_1") (pintype "passive"))
      (node (ref "J14") (pin "1") (pinfunction "1_1") (pintype "passive"))
      (node (ref "J15") (pin "1") (pinfunction "1_1") (pintype "passive"))
      (node (ref "J16") (pin "1") (pinfunction "1_1") (pintype "passive"))
      (node (ref "J17") (pin "1") (pinfunction "1_1") (pintype "passive"))
      (node (ref "J18") (pin "1") (pinfunction "1_1") (pintype "passive"))
      (node (ref "J25") (pin "2") (pinfunction "2_2") (pintype "passive"))
      (node (ref "J25") (pin "4") (pinfunction "4_4") (pintype "passive"))
    )
    (net (code "3") (name "/BTN_EN1") (class "Default")
      (node (ref "R47") (pin "1") (pinfunction "1_1") (pintype "passive"))
    )
    (net (code "4") (name "/BTN_EN2") (class "Default")
      (node (ref "R48") (pin "1") (pinfunction "1_1") (pintype "passive"))
    )
    (net (code "5") (name "/CAM_PWR") (class "Default")
      (node (ref "U4") (pin "8") (pinfunction "IO32_8") (pintype "bidirectional"))
    )
    (net (code "6") (name "/CAM_RST") (class "Default")
      (node (ref "C99") (pin "1") (pinfunction "1_1") (pintype "passive"))
      (node (ref "J30") (pin "19") (pinfunction "19_19") (pintype "passive"))
      (node (ref "R28") (pin "1") (pinfunction "1_1") (pintype "passive"))
    )
    (net (code "7") (name "/CLK") (class "Default")
      (node (ref "U4") (pin "20") (pinfunction "SCK/CLK_20") (pintype "bidirectional"))
    )
    (net (code "8") (name "/CMD") (class "Default")
      (node (ref "U4") (pin "19") (pinfunction "SCS/CMD_19") (pintype "bidirectional"))
    )
    (net (code "9") (name "/CSI_D0") (class "Default")
      (node (ref "J30") (pin "6") (pinfunction "6_6") (pintype "passive"))
      (node (ref "R173") (pin "1") (pinfunction "1_1") (pintype "passive"))
    )
    (net (code "10") (name "/CSI_D1") (class "Default")
      (node (ref "J30") (pin "4") (pinfunction "4_4") (pintype "passive"))
      (node (ref "R171") (pin "2") (pinfunction "2_2") (pintype "passive"))
    )
    (net (code "11") (name "/CSI_D2") (class "Default")
      (node (ref "J30") (pin "3") (pinfunction "3_3") (pintype "passive"))
      (node (ref "R172") (pin "2") (pinfunction "2_2") (pintype "passive"))
    )
    (net (code "12") (name "/CSI_D3") (class "Default")
      (node (ref "J30") (pin "5") (pinfunction "5_5") (pintype "passive"))
      (node (ref "U4") (pin "33") (pinfunction "IO21_33") (pintype "bidirectional"))
    )
    (net (code "13") (name "/CSI_D4") (class "Default")
      (node (ref "J30") (pin "7") (pinfunction "7_7") (pintype "passive"))
      (node (ref "U4") (pin "4") (pinfunction "SENSOR_VP_4") (pintype "input"))
    )
    (net (code "14") (name "/CSI_D5") (class "Default")
      (node (ref "J30") (pin "9") (pinfunction "9_9") (pintype "passive"))
      (node (ref "U4") (pin "5") (pinfunction "SENSOR_VN_5") (pintype "input"))
    )
    (net (code "15") (name "/CSI_D6") (class "Default")
      (node (ref "J30") (pin "11") (pinfunction "11_11") (pintype "passive"))
      (node (ref "U4") (pin "6") (pinfunction "IO34_6") (pintype "bidirectional"))
    )
    (net (code "16") (name "/CSI_D7") (class "Default")
      (node (ref "J30") (pin "13") (pinfunction "13_13") (pintype "passive"))
      (node (ref "U4") (pin "7") (pinfunction "IO35_7") (pintype "bidirectional"))
    )
    (net (code "17") (name "/CSI_HSYNC") (class "Default")
      (node (ref "J30") (pin "16") (pinfunction "16_16") (pintype "passive"))
    )
    (net (code "18") (name "/CSI_PCLK") (class "Default")
      (node (ref "C103") (pin "1") (pinfunction "1_1") (pintype "passive"))
      (node (ref "J30") (pin "8") (pinfunction "8_8") (pintype "passive"))
      (node (ref "U4") (pin "36") (pinfunction "IO22_36") (pintype "bidirectional"))
    )
    (net (code "19") (name "/CSI_VSYNC") (class "Default")
      (node (ref "J30") (pin "18") (pinfunction "18_18") (pintype "passive"))
      (node (ref "U4") (pin "10") (pinfunction "IO25_10") (pintype "bidirectional"))
    )
    (net (code "20") (name "/Cam") (class "Default")
      (node (ref "R86") (pin "1") (pinfunction "1_1") (pintype "passive"))
    )
    (net (code "21") (name "/DTR") (class "Default")
      (node (ref "Q21") (pin "2") (pinfunction "EMITTER_2") (pintype "passive"))
      (node (ref "R135") (pin "1") (pinfunction "1_1") (pintype "passive"))
    )
    (net (code "22") (name "/E0DIAG") (class "Default")
      (node (ref "R83") (pin "2") (pinfunction "2_2") (pintype "passive"))
    )
    (net (code "23") (name "/E1-") (class "Default")
      (node (ref "R61") (pin "1") (pinfunction "1_1") (pintype "passive"))
    )
    (net (code "24") (name "/E1-0") (class "Default")
      (node (ref "C34") (pin "1") (pinfunction "1_1") (pintype "passive"))
      (node (ref "R59") (pin "2") (pinfunction "2_2") (pintype "passive"))
      (node (ref "R61") (pin "2") (pinfunction "2_2") (pintype "passive"))
      (node (ref "R84") (pin "1") (pinfunction "1_1") (pintype "passive"))
    )
    (net (code "25") (name "/E1DIAG") (class "Default")
      (node (ref "R84") (pin "2") (pinfunction "2_2") (pintype "passive"))
    )
    (net (code "26") (name "/ESP_EN") (class "Default")
      (node (ref "C32") (pin "1") (pinfunction "1_1") (pintype "passive"))
      (node (ref "Q20") (pin "3") (pinfunction "COLLECTOR_3") (pintype "passive"))
      (node (ref "R136") (pin "1") (pinfunction "1_1") (pintype "passive"))
      (node (ref "R51") (pin "2") (pinfunction "2_2") (pintype "passive"))
      (node (ref "SW3") (pin "2") (pinfunction "B0_2") (pintype "passive"))
      (node (ref "SW3") (pin "3") (pinfunction "B1_3") (pintype "passive"))
    )
    (net (code "27") (name "/HS2_DATA0") (class "Default")
      (node (ref "U4") (pin "24") (pinfunction "IO2_24") (pintype "bidirectional"))
    )
    (net (code "28") (name "/HS2_DATA1") (class "Default")
      (node (ref "U4") (pin "26") (pinfunction "IO4_26") (pintype "bidirectional"))
    )
    (net (code "29") (name "/LED1") (class "Default")
      (node (ref "D9") (pin "K") (pinfunction "C_K") (pintype "passive"))
      (node (ref "U4") (pin "9") (pinfunction "IO33_9") (pintype "bidirectional"))
    )
    (net (code "30") (name "/MT_DET1") (class "Default")
      (node (ref "R44") (pin "1") (pinfunction "1_1") (pintype "passive"))
    )
    (net (code "31") (name "/MT_DET2") (class "Default")
      (node (ref "R46") (pin "1") (pinfunction "1_1") (pintype "passive"))
    )
    (net (code "32") (name "/PSRAM_CLK") (class "Default")
      (node (ref "U18") (pin "6") (pinfunction "SCLK_6") (pintype "passive"))
      (node (ref "U4") (pin "28") (pinfunction "IO17_28") (pintype "bidirectional"))
    )
    (net (code "33") (name "/RST") (class "Default")
      (node (ref "Q20") (pin "2") (pinfunction "EMITTER_2") (pintype "passive"))
      (node (ref "R137") (pin "1") (pinfunction "1_1") (pintype "passive"))
    )
    (net (code "34") (name "/RXD0") (class "Default")
      (node (ref "R54") (pin "1") (pinfunction "1_1") (pintype "passive"))
    )
    (net (code "35") (name "/SD0") (class "Default")
      (node (ref "U18") (pin "2") (pinfunction "SO/SIO1_2") (pintype "passive"))
      (node (ref "U4") (pin "21") (pinfunction "SDO/SD0_21") (pintype "bidirectional"))
    )
    (net (code "36") (name "/SD1") (class "Default")
      (node (ref "U18") (pin "5") (pinfunction "SO/SIO0_5") (pintype "passive"))
      (node (ref "U4") (pin "22") (pinfunction "SDI/SD1_22") (pintype "bidirectional"))
    )
    (net (code "37") (name "/SD2") (class "Default")
      (node (ref "U18") (pin "7") (pinfunction "SIO3_7") (pintype "passive"))
      (node (ref "U4") (pin "17") (pinfunction "SHD/SD2_17") (pintype "bidirectional"))
    )
    (net (code "38") (name "/SD3") (class "Default")
      (node (ref "U18") (pin "3") (pinfunction "SIO2_3") (pintype "passive"))
      (node (ref "U4") (pin "18") (pinfunction "SWP/SD3_18") (pintype "bidirectional"))
    )
    (net (code "39") (name "/SPI3_CS") (class "Default")
      (node (ref "R166") (pin "2") (pinfunction "2_2") (pintype "passive"))
    )
    (net (code "40") (name "/SPI3_MISO") (class "Default")
      (node (ref "U4") (pin "14") (pinfunction "IO12_14") (pintype "bidirectional"))
    )
    (net (code "41") (name "/SPI3_MOSI") (class "Default")
      (node (ref "U4") (pin "16") (pinfunction "IO13_16") (pintype "bidirectional"))
    )
    (net (code "42") (name "/SPI3_SCK") (class "Default")
      (node (ref "U4") (pin "13") (pinfunction "IO14_13") (pintype "bidirectional"))
    )
    (net (code "43") (name "/TW1_SCK") (class "Default")
      (node (ref "J30") (pin "20") (pinfunction "20_20") (pintype "passive"))
      (node (ref "R25") (pin "1") (pinfunction "1_1") (pintype "passive"))
      (node (ref "U4") (pin "12") (pinfunction "IO27_12") (pintype "bidirectional"))
    )
    (net (code "44") (name "/TW1_SDA") (class "Default")
      (node (ref "J30") (pin "22") (pinfunction "22_22") (pintype "passive"))
      (node (ref "R26") (pin "1") (pinfunction "1_1") (pintype "passive"))
      (node (ref "U4") (pin "11") (pinfunction "IO26_11") (pintype "bidirectional"))
    )
    (net (code "45") (name "/TXD0") (class "Default")
      (node (ref "R56") (pin "1") (pinfunction "1_1") (pintype "passive"))
    )
    (net (code "46") (name "/U2RXD") (class "Default")
      (node (ref "R33") (pin "2") (pinfunction "2_2") (pintype "passive"))
      (node (ref "R55") (pin "2") (pinfunction "2_2") (pintype "passive"))
      (node (ref "U18") (pin "1") (pinfunction "CS_1") (pintype "passive"))
    )
    (net (code "47") (name "/WIFI_IO0") (class "Default")
      (node (ref "C81") (pin "1") (pinfunction "1_1") (pintype "passive"))
      (node (ref "J30") (pin "12") (pinfunction "12_12") (pintype "passive"))
      (node (ref "Q21") (pin "3") (pinfunction "COLLECTOR_3") (pintype "passive"))
      (node (ref "R138") (pin "1") (pinfunction "1_1") (pintype "passive"))
      (node (ref "R139") (pin "2") (pinfunction "2_2") (pintype "passive"))
      (node (ref "SW4") (pin "2") (pinfunction "B0_2") (pintype "passive"))
      (node (ref "SW4") (pin "3") (pinfunction "B1_3") (pintype "passive"))
    )
    (net (code "48") (name "/X-") (class "Default")
      (node (ref "R52") (pin "1") (pinfunction "1_1") (pintype "passive"))
    )
    (net (code "49") (name "/X-0") (class "Default")
      (node (ref "C30") (pin "1") (pinfunction "1_1") (pintype "passive"))
      (node (ref "J17") (pin "3") (pinfunction "3_3") (pintype "passive"))
      (node (ref "R49") (pin "2") (pinfunction "2_2") (pintype "passive"))
      (node (ref "R52") (pin "2") (pinfunction "2_2") (pintype "passive"))
      (node (ref "R74") (pin "1") (pinfunction "1_1") (pintype "passive"))
    )
    (net (code "50") (name "/XDIAG") (class "Default")
      (node (ref "R74") (pin "2") (pinfunction "2_2") (pintype "passive"))
    )
    (net (code "51") (name "/Y-") (class "Default")
      (node (ref "R53") (pin "1") (pinfunction "1_1") (pintype "passive"))
    )
    (net (code "52") (name "/YDIAG") (class "Default")
      (node (ref "R80") (pin "2") (pinfunction "2_2") (pintype "passive"))
    )
    (net (code "53") (name "/Y_0") (class "Default")
      (node (ref "C31") (pin "1") (pinfunction "1_1") (pintype "passive"))
      (node (ref "J18") (pin "3") (pinfunction "3_3") (pintype "passive"))
      (node (ref "R50") (pin "2") (pinfunction "2_2") (pintype "passive"))
      (node (ref "R53") (pin "2") (pinfunction "2_2") (pintype "passive"))
      (node (ref "R80") (pin "1") (pinfunction "1_1") (pintype "passive"))
    )
    (net (code "54") (name "/Z+0") (class "Default")
      (node (ref "R83") (pin "1") (pinfunction "1_1") (pintype "passive"))
    )
    (net (code "55") (name "/Z-") (class "Default")
      (node (ref "R60") (pin "1") (pinfunction "1_1") (pintype "passive"))
    )
    (net (code "56") (name "/ZDIAG") (class "Default")
      (node (ref "R82") (pin "2") (pinfunction "2_2") (pintype "passive"))
    )
    (net (code "57") (name "/Z_0") (class "Default")
      (node (ref "C33") (pin "1") (pinfunction "1_1") (pintype "passive"))
      (node (ref "R58") (pin "2") (pinfunction "2_2") (pintype "passive"))
      (node (ref "R60") (pin "2") (pinfunction "2_2") (pintype "passive"))
      (node (ref "R82") (pin "1") (pinfunction "1_1") (pintype "passive"))
    )
    (net (code "58") (name "CSI-1.2V") (class "Default")
      (node (ref "C101") (pin "1") (pinfunction "1_1") (pintype "passive"))
      (node (ref "C102") (pin "2") (pinfunction "2_2") (pintype "passive"))
      (node (ref "J30") (pin "15") (pinfunction "15_15") (pintype "passive"))
      (node (ref "VR2") (pin "2") (pinfunction "VOUT_2") (pintype "output"))
    )
    (net (code "59") (name "CSI-2.8V") (class "Default")
      (node (ref "C96") (pin "1") (pinfunction "1_1") (pintype "passive"))
      (node (ref "C98") (pin "2") (pinfunction "2_2") (pintype "passive"))
      (node (ref "J30") (pin "21") (pinfunction "21_21") (pintype "passive"))
      (node (ref "VR1") (pin "2") (pinfunction "VOUT_2") (pintype "output"))
    )
    (net (code "60") (name "GND") (class "Default")
      (node (ref "C100") (pin "2") (pinfunction "2_2") (pintype "passive"))
      (node (ref "C101") (pin "2") (pinfunction "2_2") (pintype "passive"))
      (node (ref "C102") (pin "1") (pinfunction "1_1") (pintype "passive"))
      (node (ref "C103") (pin "2") (pinfunction "2_2") (pintype "passive"))
      (node (ref "C104") (pin "2") (pinfunction "2_2") (pintype "passive"))
      (node (ref "C105") (pin "2") (pinfunction "2_2") (pintype "passive"))
      (node (ref "C23") (pin "2") (pinfunction "2_2") (pintype "passive"))
      (node (ref "C24") (pin "2") (pinfunction "2_2") (pintype "passive"))
      (node (ref "C25") (pin "2") (pinfunction "2_2") (pintype "passive"))
      (node (ref "C26") (pin "2") (pinfunction "2_2") (pintype "passive"))
      (node (ref "C28") (pin "2") (pinfunction "2_2") (pintype "passive"))
      (node (ref "C29") (pin "2") (pinfunction "2_2") (pintype "passive"))
      (node (ref "C30") (pin "2") (pinfunction "2_2") (pintype "passive"))
      (node (ref "C31") (pin "2") (pinfunction "2_2") (pintype "passive"))
      (node (ref "C32") (pin "2") (pinfunction "2_2") (pintype "passive"))
      (node (ref "C33") (pin "2") (pinfunction "2_2") (pintype "passive"))
      (node (ref "C34") (pin "2") (pinfunction "2_2") (pintype "passive"))
      (node (ref "C81") (pin "2") (pinfunction "2_2") (pintype "passive"))
      (node (ref "C96") (pin "2") (pinfunction "2_2") (pintype "passive"))
      (node (ref "C97") (pin "2") (pinfunction "2_2") (pintype "passive"))
      (node (ref "C98") (pin "1") (pinfunction "1_1") (pintype "passive"))
      (node (ref "C99") (pin "2") (pinfunction "2_2") (pintype "passive"))
      (node (ref "J13") (pin "2") (pinfunction "2_2") (pintype "passive"))
      (node (ref "J14") (pin "2") (pinfunction "2_2") (pintype "passive"))
      (node (ref "J15") (pin "2") (pinfunction "2_2") (pintype "passive"))
      (node (ref "J16") (pin "2") (pinfunction "2_2") (pintype "passive"))
      (node (ref "J17") (pin "2") (pinfunction "2_2") (pintype "passive"))
      (node (ref "J18") (pin "2") (pinfunction "2_2") (pintype "passive"))
      (node (ref "J25") (pin "1") (pinfunction "1_1") (pintype "passive"))
      (node (ref "J25") (pin "3") (pinfunction "3_3") (pintype "passive"))
      (node (ref "J25") (pin "5") (pinfunction "5_5") (pintype "passive"))
      (node (ref "J25") (pin "7") (pinfunction "7_7") (pintype "passive"))
      (node (ref "J25") (pin "9") (pinfunction "9_9") (pintype "passive"))
      (node (ref "J30") (pin "10") (pinfunction "10_10") (pintype "passive"))
      (node (ref "J30") (pin "23") (pinfunction "23_23") (pintype "passive"))
      (node (ref "J30") (pin "S1") (pinfunction "SHIELD_S1") (pintype "passive"))
      (node (ref "J30") (pin "S2") (pinfunction "SHIELD_S2") (pintype "passive"))
      (node (ref "R32") (pin "2") (pinfunction "2_2") (pintype "passive"))
      (node (ref "SW3") (pin "1") (pinfunction "A0_1") (pintype "passive"))
      (node (ref "SW3") (pin "4") (pinfunction "A1_4") (pintype "passive"))
      (node (ref "SW4") (pin "1") (pinfunction "A0_1") (pintype "passive"))
      (node (ref "SW4") (pin "4") (pinfunction "A1_4") (pintype "passive"))
      (node (ref "U18") (pin "4") (pinfunction "VSS_4") (pintype "passive"))
      (node (ref "U4") (pin "1") (pinfunction "GND_1") (pintype "power_in"))
      (node (ref "U4") (pin "15") (pinfunction "GND_15") (pintype "power_in"))
      (node (ref "U4") (pin "38") (pinfunction "GND_38") (pintype "power_in"))
      (node (ref "U4") (pin "39") (pinfunction "GND_39") (pintype "power_in"))
      (node (ref "VR1") (pin "1") (pinfunction "VSS_1") (pintype "power_in"))
      (node (ref "VR2") (pin "1") (pinfunction "VSS_1") (pintype "power_in"))
    )
    (net (code "61") (name "Net-(C23-Pad1)") (class "Default")
      (node (ref "C23") (pin "1") (pinfunction "1_1") (pintype "passive"))
      (node (ref "J13") (pin "3") (pinfunction "3_3") (pintype "passive"))
      (node (ref "R40") (pin "2") (pinfunction "2_2") (pintype "passive"))
      (node (ref "R44") (pin "2") (pinfunction "2_2") (pintype "passive"))
    )
    (net (code "62") (name "Net-(C24-Pad1)") (class "Default")
      (node (ref "C24") (pin "1") (pinfunction "1_1") (pintype "passive"))
      (node (ref "J14") (pin "3") (pinfunction "3_3") (pintype "passive"))
      (node (ref "R41") (pin "2") (pinfunction "2_2") (pintype "passive"))
      (node (ref "R46") (pin "2") (pinfunction "2_2") (pintype "passive"))
    )
    (net (code "63") (name "Net-(C25-Pad1)") (class "Default")
      (node (ref "C25") (pin "1") (pinfunction "1_1") (pintype "passive"))
      (node (ref "J15") (pin "3") (pinfunction "3_3") (pintype "passive"))
      (node (ref "R42") (pin "2") (pinfunction "2_2") (pintype "passive"))
      (node (ref "R47") (pin "2") (pinfunction "2_2") (pintype "passive"))
    )
    (net (code "64") (name "Net-(C26-Pad1)") (class "Default")
      (node (ref "C26") (pin "1") (pinfunction "1_1") (pintype "passive"))
      (node (ref "J16") (pin "3") (pinfunction "3_3") (pintype "passive"))
      (node (ref "R43") (pin "2") (pinfunction "2_2") (pintype "passive"))
      (node (ref "R48") (pin "2") (pinfunction "2_2") (pintype "passive"))
    )
    (net (code "65") (name "Net-(D9-PadA)") (class "Default")
      (node (ref "D9") (pin "A") (pinfunction "A_A") (pintype "passive"))
      (node (ref "R24") (pin "2") (pinfunction "2_2") (pintype "passive"))
    )
    (net (code "66") (name "Net-(J30-Pad17)") (class "Default")
      (node (ref "J30") (pin "17") (pinfunction "17_17") (pintype "passive"))
      (node (ref "R32") (pin "1") (pinfunction "1_1") (pintype "passive"))
    )
    (net (code "67") (name "Net-(Q8-G)") (class "Default")
      (node (ref "Q8") (pin "1") (pinfunction "G_1") (pintype "passive"))
      (node (ref "R85") (pin "2") (pinfunction "2_2") (pintype "passive"))
      (node (ref "R86") (pin "2") (pinfunction "2_2") (pintype "passive"))
    )
    (net (code "68") (name "Net-(Q8-S)") (class "Default")
      (node (ref "C100") (pin "1") (pinfunction "1_1") (pintype "passive"))
      (node (ref "C97") (pin "1") (pinfunction "1_1") (pintype "passive"))
      (node (ref "Q8") (pin "2") (pinfunction "S_2") (pintype "passive"))
      (node (ref "VR1") (pin "3") (pinfunction "VIN_3") (pintype "input"))
      (node (ref "VR2") (pin "3") (pinfunction "VIN_3") (pintype "input"))
    )
    (net (code "69") (name "Net-(Q20-BASE)") (class "Default")
      (node (ref "Q20") (pin "1") (pinfunction "BASE_1") (pintype "passive"))
      (node (ref "R135") (pin "2") (pinfunction "2_2") (pintype "passive"))
    )
    (net (code "70") (name "Net-(Q21-BASE)") (class "Default")
      (node (ref "Q21") (pin "1") (pinfunction "BASE_1") (pintype "passive"))
      (node (ref "R137") (pin "2") (pinfunction "2_2") (pintype "passive"))
    )
    (net (code "71") (name "Net-(U4-EN)") (class "Default")
      (node (ref "R136") (pin "2") (pinfunction "2_2") (pintype "passive"))
      (node (ref "U4") (pin "3") (pinfunction "EN_3") (pintype "input"))
    )
    (net (code "72") (name "Net-(U4-IO0)") (class "Default")
      (node (ref "R138") (pin "2") (pinfunction "2_2") (pintype "passive"))
      (node (ref "U4") (pin "25") (pinfunction "IO0_25") (pintype "bidirectional"))
    )
    (net (code "73") (name "Net-(U4-IO5)") (class "Default")
      (node (ref "R173") (pin "2") (pinfunction "2_2") (pintype "passive"))
      (node (ref "U4") (pin "29") (pinfunction "IO5_29") (pintype "bidirectional"))
    )
    (net (code "74") (name "Net-(U4-IO15)") (class "Default")
      (node (ref "R166") (pin "1") (pinfunction "1_1") (pintype "passive"))
      (node (ref "U4") (pin "23") (pinfunction "IO15_23") (pintype "bidirectional"))
    )
    (net (code "75") (name "Net-(U4-IO16)") (class "Default")
      (node (ref "R55") (pin "1") (pinfunction "1_1") (pintype "passive"))
      (node (ref "U4") (pin "27") (pinfunction "IO16_27") (pintype "bidirectional"))
    )
    (net (code "76") (name "Net-(U4-IO18)") (class "Default")
      (node (ref "R171") (pin "1") (pinfunction "1_1") (pintype "passive"))
      (node (ref "U4") (pin "30") (pinfunction "IO18_30") (pintype "bidirectional"))
    )
    (net (code "77") (name "Net-(U4-IO19)") (class "Default")
      (node (ref "R172") (pin "1") (pinfunction "1_1") (pintype "passive"))
      (node (ref "U4") (pin "31") (pinfunction "IO19_31") (pintype "bidirectional"))
    )
    (net (code "78") (name "Net-(U4-RXD0)") (class "Default")
      (node (ref "R56") (pin "2") (pinfunction "2_2") (pintype "passive"))
      (node (ref "U4") (pin "34") (pinfunction "RXD0_34") (pintype "bidirectional"))
    )
    (net (code "79") (name "Net-(U4-TXD0)") (class "Default")
      (node (ref "R54") (pin "2") (pinfunction "2_2") (pintype "passive"))
      (node (ref "U4") (pin "35") (pinfunction "TXD0_35") (pintype "bidirectional"))
    )
    (net (code "80") (name "unconnected-(J30-Pad1)") (class "Default")
      (node (ref "J30") (pin "1") (pinfunction "1_1") (pintype "passive"))
    )
    (net (code "81") (name "unconnected-(J30-Pad2)") (class "Default")
      (node (ref "J30") (pin "2") (pinfunction "2_2") (pintype "passive"))
    )
    (net (code "82") (name "unconnected-(J30-Pad24)") (class "Default")
      (node (ref "J30") (pin "24") (pinfunction "24_24") (pintype "passive"))
    )
    (net (code "83") (name "unconnected-(U4-IO23-Pad37)") (class "Default")
      (node (ref "U4") (pin "37") (pinfunction "IO23_37") (pintype "bidirectional"))
    )
  )
)
